# schematic.net
KiCad netlist of a schematic drawn in EAGLE
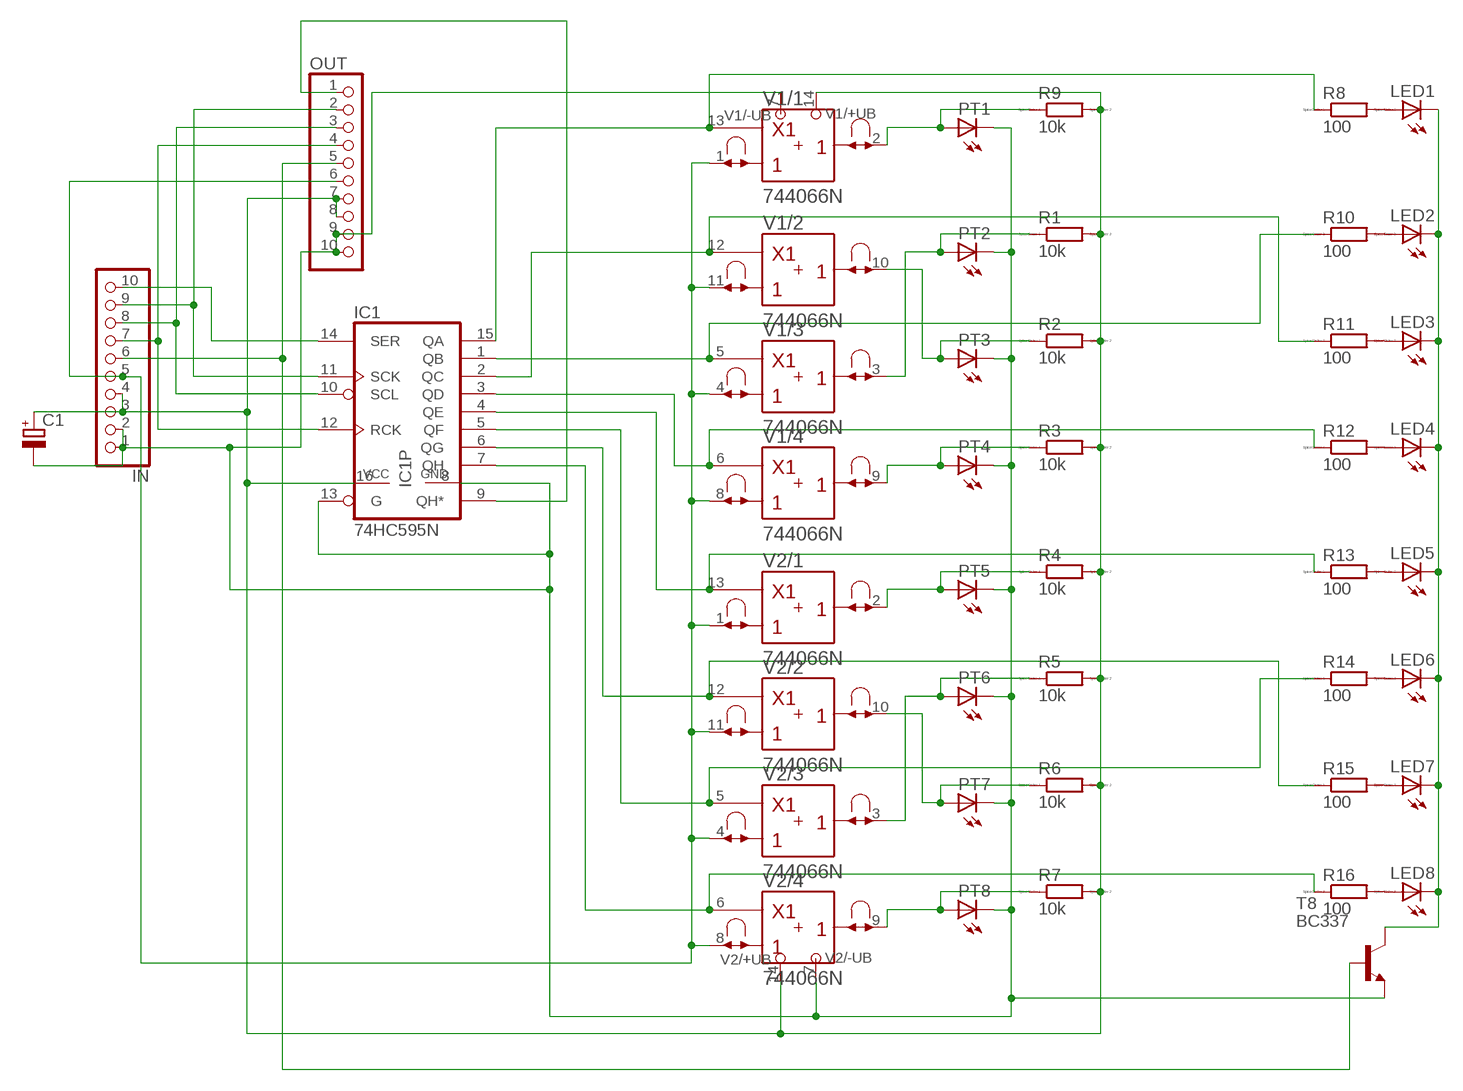
[diagram p0: schematic, sheet 1]

(export (version "E")
  (design (tool "Eeschema 10.0.6"))
  (components
    (comp (ref "C1")
      (value "CPOL-EUE5-10.5")
      (footprint "eagle-import:E5-10,5")
      (libsource (lib "eagle-import") (part "CPOL-EUE5-10.5"))
    )
    (comp (ref "IC1")
      (value "74HC595N")
      (footprint "eagle-import:DIL16")
      (libsource (lib "eagle-import") (part "74595NHC"))
    )
    (comp (ref "IN")
      (value "PINHD-1X10/90")
      (footprint "eagle-import:1X10_90")
      (libsource (lib "eagle-import") (part "PINHD-1X10/90"))
    )
    (comp (ref "LED1")
      (value "LED5MM")
      (footprint "eagle-import:LED5MM")
      (libsource (lib "eagle-import") (part "LED5MM"))
    )
    (comp (ref "LED2")
      (value "LED5MM")
      (footprint "eagle-import:LED5MM")
      (libsource (lib "eagle-import") (part "LED5MM"))
    )
    (comp (ref "LED3")
      (value "LED5MM")
      (footprint "eagle-import:LED5MM")
      (libsource (lib "eagle-import") (part "LED5MM"))
    )
    (comp (ref "LED4")
      (value "LED5MM")
      (footprint "eagle-import:LED5MM")
      (libsource (lib "eagle-import") (part "LED5MM"))
    )
    (comp (ref "LED5")
      (value "LED5MM")
      (footprint "eagle-import:LED5MM")
      (libsource (lib "eagle-import") (part "LED5MM"))
    )
    (comp (ref "LED6")
      (value "LED5MM")
      (footprint "eagle-import:LED5MM")
      (libsource (lib "eagle-import") (part "LED5MM"))
    )
    (comp (ref "LED7")
      (value "LED5MM")
      (footprint "eagle-import:LED5MM")
      (libsource (lib "eagle-import") (part "LED5MM"))
    )
    (comp (ref "LED8")
      (value "LED5MM")
      (footprint "eagle-import:LED5MM")
      (libsource (lib "eagle-import") (part "LED5MM"))
    )
    (comp (ref "OUT")
      (value "PINHD-1X10/90")
      (footprint "eagle-import:1X10_90")
      (libsource (lib "eagle-import") (part "PINHD-1X10/90"))
    )
    (comp (ref "PT1")
      (value "LED5MM")
      (footprint "eagle-import:LED5MM")
      (libsource (lib "eagle-import") (part "LED5MM"))
    )
    (comp (ref "PT2")
      (value "LED5MM")
      (footprint "eagle-import:LED5MM")
      (libsource (lib "eagle-import") (part "LED5MM"))
    )
    (comp (ref "PT3")
      (value "LED5MM")
      (footprint "eagle-import:LED5MM")
      (libsource (lib "eagle-import") (part "LED5MM"))
    )
    (comp (ref "PT4")
      (value "LED5MM")
      (footprint "eagle-import:LED5MM")
      (libsource (lib "eagle-import") (part "LED5MM"))
    )
    (comp (ref "PT5")
      (value "LED5MM")
      (footprint "eagle-import:LED5MM")
      (libsource (lib "eagle-import") (part "LED5MM"))
    )
    (comp (ref "PT6")
      (value "LED5MM")
      (footprint "eagle-import:LED5MM")
      (libsource (lib "eagle-import") (part "LED5MM"))
    )
    (comp (ref "PT7")
      (value "LED5MM")
      (footprint "eagle-import:LED5MM")
      (libsource (lib "eagle-import") (part "LED5MM"))
    )
    (comp (ref "PT8")
      (value "LED5MM")
      (footprint "eagle-import:LED5MM")
      (libsource (lib "eagle-import") (part "LED5MM"))
    )
    (comp (ref "R1")
      (value "10k")
      (footprint "eagle-import:0204_7")
      (libsource (lib "eagle-import") (part "R0204/7"))
    )
    (comp (ref "R2")
      (value "10k")
      (footprint "eagle-import:0204_7")
      (libsource (lib "eagle-import") (part "R0204/7"))
    )
    (comp (ref "R3")
      (value "10k")
      (footprint "eagle-import:0204_7")
      (libsource (lib "eagle-import") (part "R0204/7"))
    )
    (comp (ref "R4")
      (value "10k")
      (footprint "eagle-import:0204_7")
      (libsource (lib "eagle-import") (part "R0204/7"))
    )
    (comp (ref "R5")
      (value "10k")
      (footprint "eagle-import:0204_7")
      (libsource (lib "eagle-import") (part "R0204/7"))
    )
    (comp (ref "R6")
      (value "10k")
      (footprint "eagle-import:0204_7")
      (libsource (lib "eagle-import") (part "R0204/7"))
    )
    (comp (ref "R7")
      (value "10k")
      (footprint "eagle-import:0204_7")
      (libsource (lib "eagle-import") (part "R0204/7"))
    )
    (comp (ref "R8")
      (value "100")
      (footprint "eagle-import:0204_7")
      (libsource (lib "eagle-import") (part "R0204/7"))
    )
    (comp (ref "R9")
      (value "10k")
      (footprint "eagle-import:0204_7")
      (libsource (lib "eagle-import") (part "R0204/7"))
    )
    (comp (ref "R10")
      (value "100")
      (footprint "eagle-import:0204_7")
      (libsource (lib "eagle-import") (part "R0204/7"))
    )
    (comp (ref "R11")
      (value "100")
      (footprint "eagle-import:0204_7")
      (libsource (lib "eagle-import") (part "R0204/7"))
    )
    (comp (ref "R12")
      (value "100")
      (footprint "eagle-import:0204_7")
      (libsource (lib "eagle-import") (part "R0204/7"))
    )
    (comp (ref "R13")
      (value "100")
      (footprint "eagle-import:0204_7")
      (libsource (lib "eagle-import") (part "R0204/7"))
    )
    (comp (ref "R14")
      (value "100")
      (footprint "eagle-import:0204_7")
      (libsource (lib "eagle-import") (part "R0204/7"))
    )
    (comp (ref "R15")
      (value "100")
      (footprint "eagle-import:0204_7")
      (libsource (lib "eagle-import") (part "R0204/7"))
    )
    (comp (ref "R16")
      (value "100")
      (footprint "eagle-import:0204_7")
      (libsource (lib "eagle-import") (part "R0204/7"))
    )
    (comp (ref "T8")
      (value "BC337")
      (footprint "eagle-import:TO92")
      (libsource (lib "eagle-import") (part "BC337"))
    )
    (comp (ref "V1")
      (value "744066N")
      (footprint "eagle-import:DIL14")
      (libsource (lib "eagle-import") (part "744066N"))
    )
    (comp (ref "V2")
      (value "744066N")
      (footprint "eagle-import:DIL14")
      (libsource (lib "eagle-import") (part "744066N"))
    )
  )
  (nets
    (net (code "1") (name "Net-(IC1A-G)") (class "Default")
      (node (ref "C1") (pin "-") (pinfunction "-_-") (pintype "passive"))
      (node (ref "IC1") (pin "13") (pinfunction "G_13") (pintype "input"))
      (node (ref "IC1") (pin "8") (pinfunction "GND_8") (pintype "power_in"))
      (node (ref "IN") (pin "1") (pinfunction "1_1") (pintype "passive"))
      (node (ref "IN") (pin "2") (pinfunction "2_2") (pintype "passive"))
      (node (ref "OUT") (pin "10") (pinfunction "10_10") (pintype "passive"))
      (node (ref "OUT") (pin "9") (pinfunction "9_9") (pintype "passive"))
      (node (ref "PT1") (pin "K") (pinfunction "C_K") (pintype "passive"))
      (node (ref "PT2") (pin "K") (pinfunction "C_K") (pintype "passive"))
      (node (ref "PT3") (pin "K") (pinfunction "C_K") (pintype "passive"))
      (node (ref "PT4") (pin "K") (pinfunction "C_K") (pintype "passive"))
      (node (ref "PT5") (pin "K") (pinfunction "C_K") (pintype "passive"))
      (node (ref "PT6") (pin "K") (pinfunction "C_K") (pintype "passive"))
      (node (ref "PT7") (pin "K") (pinfunction "C_K") (pintype "passive"))
      (node (ref "PT8") (pin "K") (pinfunction "C_K") (pintype "passive"))
      (node (ref "T8") (pin "1") (pinfunction "E_1") (pintype "passive"))
      (node (ref "V1") (pin "7") (pinfunction "-UB_7") (pintype "power_in"))
      (node (ref "V2") (pin "7") (pinfunction "-UB_7") (pintype "power_in"))
    )
    (net (code "2") (name "Net-(IC1A-QA)") (class "Default")
      (node (ref "IC1") (pin "15") (pinfunction "QA_15") (pintype "tri_state"))
      (node (ref "R8") (pin "1") (pinfunction "1_1") (pintype "passive"))
      (node (ref "V1") (pin "13") (pinfunction "C_13") (pintype "input"))
    )
    (net (code "3") (name "Net-(IC1A-QB)") (class "Default")
      (node (ref "IC1") (pin "1") (pinfunction "QB_1") (pintype "tri_state"))
      (node (ref "R10") (pin "1") (pinfunction "1_1") (pintype "passive"))
      (node (ref "V1") (pin "5") (pinfunction "C_5") (pintype "input"))
    )
    (net (code "4") (name "Net-(IC1A-QC)") (class "Default")
      (node (ref "IC1") (pin "2") (pinfunction "QC_2") (pintype "tri_state"))
      (node (ref "R11") (pin "1") (pinfunction "1_1") (pintype "passive"))
      (node (ref "V1") (pin "12") (pinfunction "C_12") (pintype "input"))
    )
    (net (code "5") (name "Net-(IC1A-QD)") (class "Default")
      (node (ref "IC1") (pin "3") (pinfunction "QD_3") (pintype "tri_state"))
      (node (ref "R12") (pin "1") (pinfunction "1_1") (pintype "passive"))
      (node (ref "V1") (pin "6") (pinfunction "C_6") (pintype "input"))
    )
    (net (code "6") (name "Net-(IC1A-QE)") (class "Default")
      (node (ref "IC1") (pin "4") (pinfunction "QE_4") (pintype "tri_state"))
      (node (ref "R13") (pin "1") (pinfunction "1_1") (pintype "passive"))
      (node (ref "V2") (pin "13") (pinfunction "C_13") (pintype "input"))
    )
    (net (code "7") (name "Net-(IC1A-QF)") (class "Default")
      (node (ref "IC1") (pin "5") (pinfunction "QF_5") (pintype "tri_state"))
      (node (ref "R14") (pin "1") (pinfunction "1_1") (pintype "passive"))
      (node (ref "V2") (pin "5") (pinfunction "C_5") (pintype "input"))
    )
    (net (code "8") (name "Net-(IC1A-QG)") (class "Default")
      (node (ref "IC1") (pin "6") (pinfunction "QG_6") (pintype "tri_state"))
      (node (ref "R15") (pin "1") (pinfunction "1_1") (pintype "passive"))
      (node (ref "V2") (pin "12") (pinfunction "C_12") (pintype "input"))
    )
    (net (code "9") (name "Net-(IC1A-QH)") (class "Default")
      (node (ref "IC1") (pin "7") (pinfunction "QH_7") (pintype "tri_state"))
      (node (ref "R16") (pin "1") (pinfunction "1_1") (pintype "passive"))
      (node (ref "V2") (pin "6") (pinfunction "C_6") (pintype "input"))
    )
    (net (code "10") (name "Net-(IC1A-QH*)") (class "Default")
      (node (ref "IC1") (pin "9") (pinfunction "QH*_9") (pintype "tri_state"))
      (node (ref "OUT") (pin "1") (pinfunction "1_1") (pintype "passive"))
    )
    (net (code "11") (name "Net-(IC1A-RCK)") (class "Default")
      (node (ref "IC1") (pin "12") (pinfunction "RCK_12") (pintype "input"))
      (node (ref "IN") (pin "7") (pinfunction "7_7") (pintype "passive"))
      (node (ref "OUT") (pin "4") (pinfunction "4_4") (pintype "passive"))
    )
    (net (code "12") (name "Net-(IC1A-SCK)") (class "Default")
      (node (ref "IC1") (pin "11") (pinfunction "SCK_11") (pintype "input"))
      (node (ref "IN") (pin "9") (pinfunction "9_9") (pintype "passive"))
      (node (ref "OUT") (pin "2") (pinfunction "2_2") (pintype "passive"))
    )
    (net (code "13") (name "Net-(IC1A-SCL)") (class "Default")
      (node (ref "IC1") (pin "10") (pinfunction "SCL_10") (pintype "input"))
      (node (ref "IN") (pin "8") (pinfunction "8_8") (pintype "passive"))
      (node (ref "OUT") (pin "3") (pinfunction "3_3") (pintype "passive"))
    )
    (net (code "14") (name "Net-(IC1A-SER)") (class "Default")
      (node (ref "IC1") (pin "14") (pinfunction "SER_14") (pintype "input"))
      (node (ref "IN") (pin "10") (pinfunction "10_10") (pintype "passive"))
    )
    (net (code "15") (name "Net-(IC1B-VCC)") (class "Default")
      (node (ref "C1") (pin "+") (pinfunction "+_+") (pintype "passive"))
      (node (ref "IC1") (pin "16") (pinfunction "VCC_16") (pintype "power_in"))
      (node (ref "IN") (pin "3") (pinfunction "3_3") (pintype "passive"))
      (node (ref "IN") (pin "4") (pinfunction "4_4") (pintype "passive"))
      (node (ref "OUT") (pin "7") (pinfunction "7_7") (pintype "passive"))
      (node (ref "OUT") (pin "8") (pinfunction "8_8") (pintype "passive"))
      (node (ref "R1") (pin "2") (pinfunction "2_2") (pintype "passive"))
      (node (ref "R2") (pin "2") (pinfunction "2_2") (pintype "passive"))
      (node (ref "R3") (pin "2") (pinfunction "2_2") (pintype "passive"))
      (node (ref "R4") (pin "2") (pinfunction "2_2") (pintype "passive"))
      (node (ref "R5") (pin "2") (pinfunction "2_2") (pintype "passive"))
      (node (ref "R6") (pin "2") (pinfunction "2_2") (pintype "passive"))
      (node (ref "R7") (pin "2") (pinfunction "2_2") (pintype "passive"))
      (node (ref "R9") (pin "2") (pinfunction "2_2") (pintype "passive"))
      (node (ref "V1") (pin "14") (pinfunction "+UB_14") (pintype "power_in"))
      (node (ref "V2") (pin "14") (pinfunction "+UB_14") (pintype "power_in"))
    )
    (net (code "16") (name "Net-(LED1-C)") (class "Default")
      (node (ref "LED1") (pin "K") (pinfunction "C_K") (pintype "passive"))
      (node (ref "LED2") (pin "K") (pinfunction "C_K") (pintype "passive"))
      (node (ref "LED3") (pin "K") (pinfunction "C_K") (pintype "passive"))
      (node (ref "LED4") (pin "K") (pinfunction "C_K") (pintype "passive"))
      (node (ref "LED5") (pin "K") (pinfunction "C_K") (pintype "passive"))
      (node (ref "LED6") (pin "K") (pinfunction "C_K") (pintype "passive"))
      (node (ref "LED7") (pin "K") (pinfunction "C_K") (pintype "passive"))
      (node (ref "LED8") (pin "K") (pinfunction "C_K") (pintype "passive"))
      (node (ref "T8") (pin "3") (pinfunction "C_3") (pintype "passive"))
    )
    (net (code "17") (name "Net-(LED1-PadA)") (class "Default")
      (node (ref "LED1") (pin "A") (pinfunction "A_A") (pintype "passive"))
      (node (ref "R8") (pin "2") (pinfunction "2_2") (pintype "passive"))
    )
    (net (code "18") (name "Net-(LED2-PadA)") (class "Default")
      (node (ref "LED2") (pin "A") (pinfunction "A_A") (pintype "passive"))
      (node (ref "R10") (pin "2") (pinfunction "2_2") (pintype "passive"))
    )
    (net (code "19") (name "Net-(LED3-PadA)") (class "Default")
      (node (ref "LED3") (pin "A") (pinfunction "A_A") (pintype "passive"))
      (node (ref "R11") (pin "2") (pinfunction "2_2") (pintype "passive"))
    )
    (net (code "20") (name "Net-(LED4-PadA)") (class "Default")
      (node (ref "LED4") (pin "A") (pinfunction "A_A") (pintype "passive"))
      (node (ref "R12") (pin "2") (pinfunction "2_2") (pintype "passive"))
    )
    (net (code "21") (name "Net-(LED5-PadA)") (class "Default")
      (node (ref "LED5") (pin "A") (pinfunction "A_A") (pintype "passive"))
      (node (ref "R13") (pin "2") (pinfunction "2_2") (pintype "passive"))
    )
    (net (code "22") (name "Net-(LED6-PadA)") (class "Default")
      (node (ref "LED6") (pin "A") (pinfunction "A_A") (pintype "passive"))
      (node (ref "R14") (pin "2") (pinfunction "2_2") (pintype "passive"))
    )
    (net (code "23") (name "Net-(LED7-PadA)") (class "Default")
      (node (ref "LED7") (pin "A") (pinfunction "A_A") (pintype "passive"))
      (node (ref "R15") (pin "2") (pinfunction "2_2") (pintype "passive"))
    )
    (net (code "24") (name "Net-(LED8-PadA)") (class "Default")
      (node (ref "LED8") (pin "A") (pinfunction "A_A") (pintype "passive"))
      (node (ref "R16") (pin "2") (pinfunction "2_2") (pintype "passive"))
    )
    (net (code "25") (name "Net-(T8-B)") (class "Default")
      (node (ref "IN") (pin "6") (pinfunction "6_6") (pintype "passive"))
      (node (ref "OUT") (pin "5") (pinfunction "5_5") (pintype "passive"))
      (node (ref "T8") (pin "2") (pinfunction "B_2") (pintype "passive"))
    )
    (net (code "26") (name "Net-(V1C-A)") (class "Default")
      (node (ref "IN") (pin "5") (pinfunction "5_5") (pintype "passive"))
      (node (ref "OUT") (pin "6") (pinfunction "6_6") (pintype "passive"))
      (node (ref "V1") (pin "1") (pinfunction "A_1") (pintype "passive"))
      (node (ref "V1") (pin "11") (pinfunction "A_11") (pintype "passive"))
      (node (ref "V1") (pin "4") (pinfunction "A_4") (pintype "passive"))
      (node (ref "V1") (pin "8") (pinfunction "A_8") (pintype "passive"))
      (node (ref "V2") (pin "1") (pinfunction "A_1") (pintype "passive"))
      (node (ref "V2") (pin "11") (pinfunction "A_11") (pintype "passive"))
      (node (ref "V2") (pin "4") (pinfunction "A_4") (pintype "passive"))
      (node (ref "V2") (pin "8") (pinfunction "A_8") (pintype "passive"))
    )
    (net (code "27") (name "Net-(V1C-B)") (class "Default")
      (node (ref "PT1") (pin "A") (pinfunction "A_A") (pintype "passive"))
      (node (ref "R9") (pin "1") (pinfunction "1_1") (pintype "passive"))
      (node (ref "V1") (pin "2") (pinfunction "B_2") (pintype "passive"))
    )
    (net (code "28") (name "Net-(V1D-B)") (class "Default")
      (node (ref "PT3") (pin "A") (pinfunction "A_A") (pintype "passive"))
      (node (ref "R2") (pin "1") (pinfunction "1_1") (pintype "passive"))
      (node (ref "V1") (pin "10") (pinfunction "B_10") (pintype "passive"))
    )
    (net (code "29") (name "Net-(V1E-B)") (class "Default")
      (node (ref "PT2") (pin "A") (pinfunction "A_A") (pintype "passive"))
      (node (ref "R1") (pin "1") (pinfunction "1_1") (pintype "passive"))
      (node (ref "V1") (pin "3") (pinfunction "B_3") (pintype "passive"))
    )
    (net (code "30") (name "Net-(V1F-B)") (class "Default")
      (node (ref "PT4") (pin "A") (pinfunction "A_A") (pintype "passive"))
      (node (ref "R3") (pin "1") (pinfunction "1_1") (pintype "passive"))
      (node (ref "V1") (pin "9") (pinfunction "B_9") (pintype "passive"))
    )
    (net (code "31") (name "Net-(V2C-B)") (class "Default")
      (node (ref "PT5") (pin "A") (pinfunction "A_A") (pintype "passive"))
      (node (ref "R4") (pin "1") (pinfunction "1_1") (pintype "passive"))
      (node (ref "V2") (pin "2") (pinfunction "B_2") (pintype "passive"))
    )
    (net (code "32") (name "Net-(V2D-B)") (class "Default")
      (node (ref "PT7") (pin "A") (pinfunction "A_A") (pintype "passive"))
      (node (ref "R6") (pin "1") (pinfunction "1_1") (pintype "passive"))
      (node (ref "V2") (pin "10") (pinfunction "B_10") (pintype "passive"))
    )
    (net (code "33") (name "Net-(V2E-B)") (class "Default")
      (node (ref "PT6") (pin "A") (pinfunction "A_A") (pintype "passive"))
      (node (ref "R5") (pin "1") (pinfunction "1_1") (pintype "passive"))
      (node (ref "V2") (pin "3") (pinfunction "B_3") (pintype "passive"))
    )
    (net (code "34") (name "Net-(V2F-B)") (class "Default")
      (node (ref "PT8") (pin "A") (pinfunction "A_A") (pintype "passive"))
      (node (ref "R7") (pin "1") (pinfunction "1_1") (pintype "passive"))
      (node (ref "V2") (pin "9") (pinfunction "B_9") (pintype "passive"))
    )
  )
)
